# panel.net
KiCad netlist of a schematic drawn in EAGLE
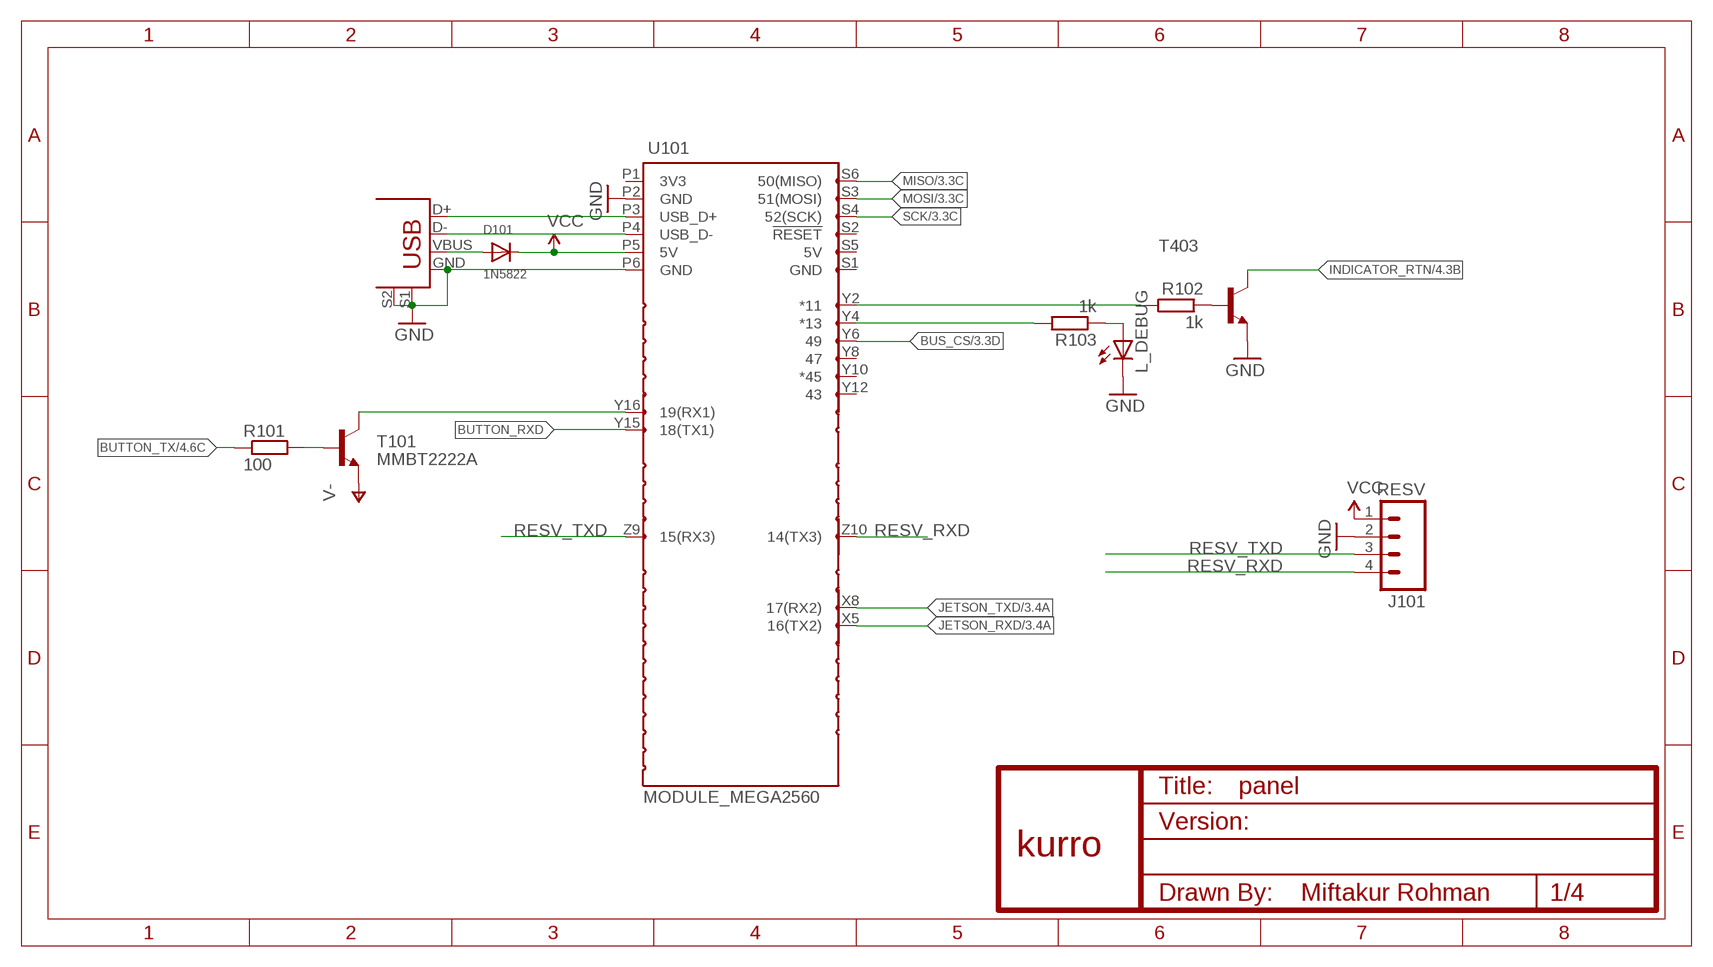
[diagram p0: schematic, sheet 1]
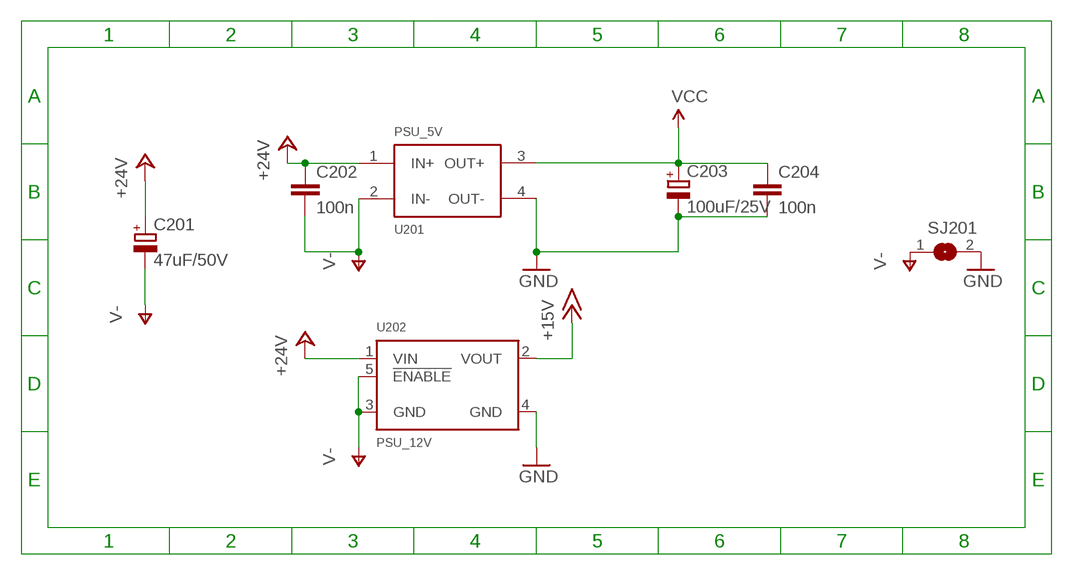
[diagram p1: schematic, sheet 2]
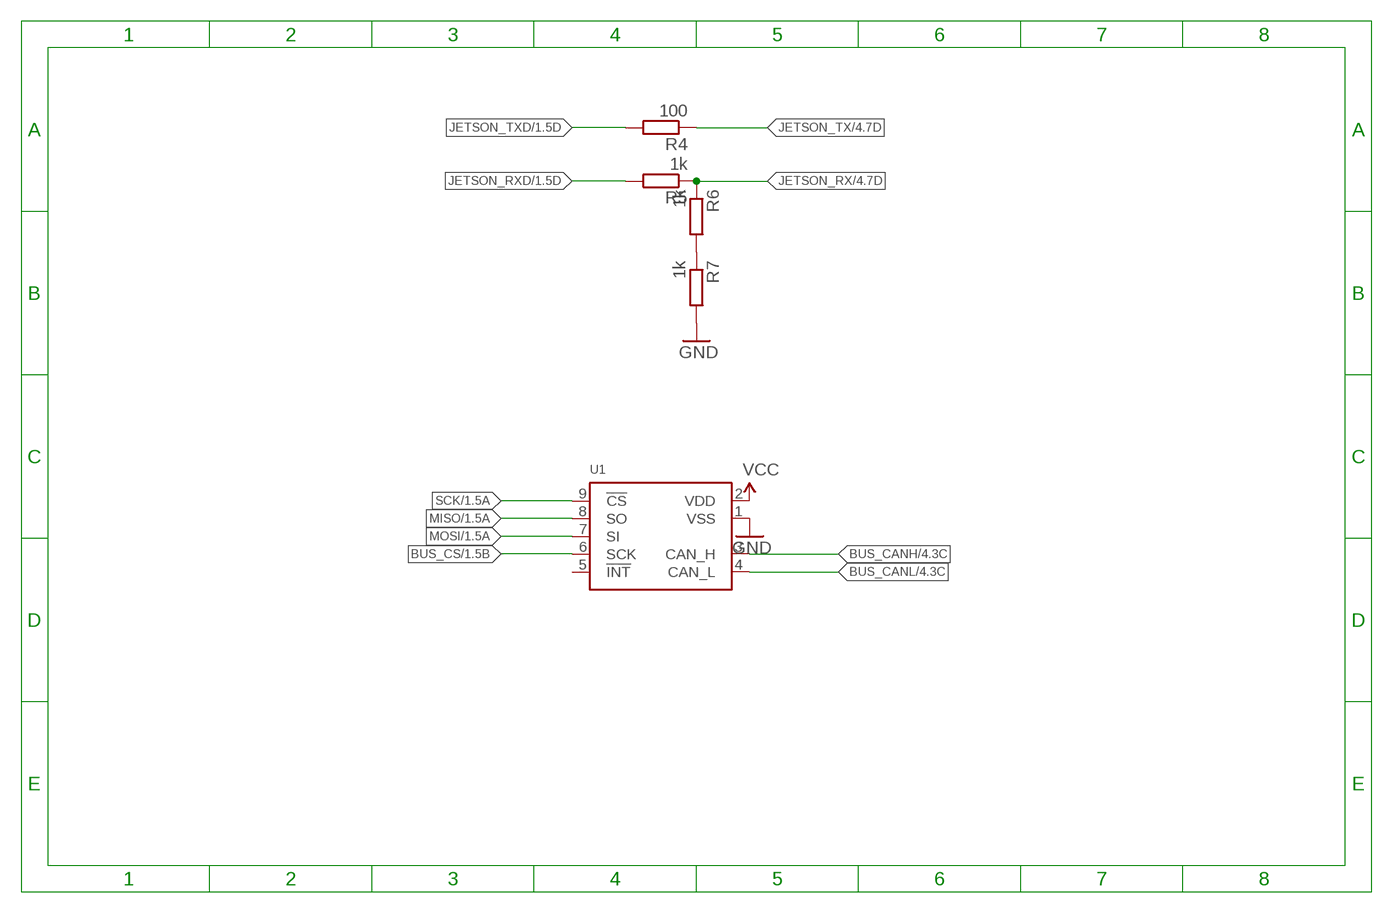
[diagram p2: schematic, sheet 3]
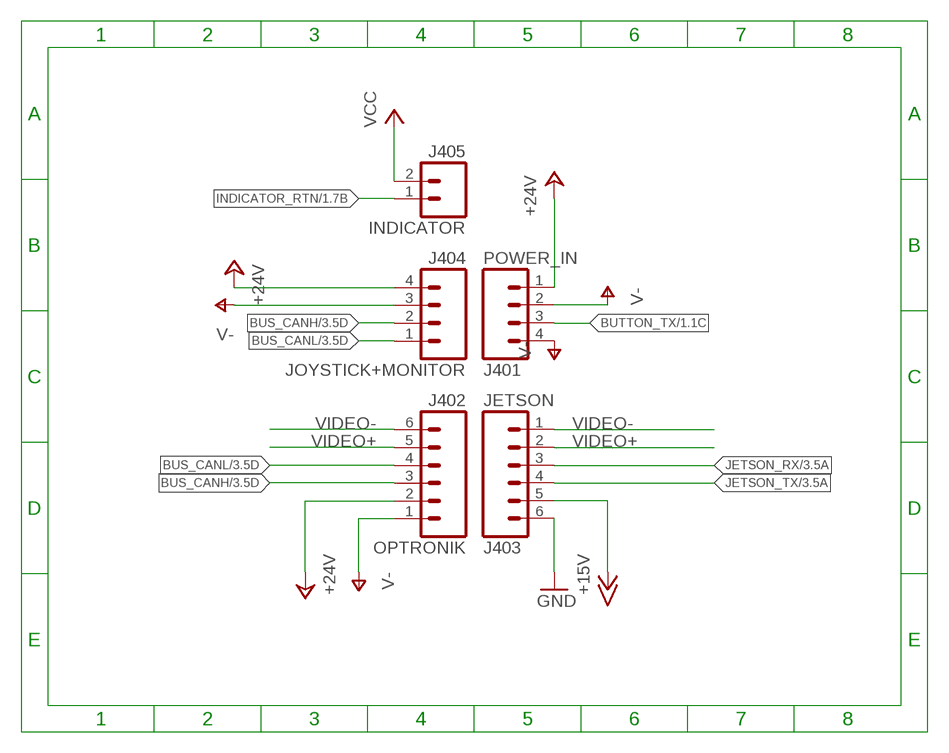
[diagram p3: schematic, sheet 4]

(export (version "E")
  (design (tool "Eeschema 10.0.6"))
  (components
    (comp (ref "D101")
      (value "1N5822")
      (footprint "eagle-import:SMADIODE")
      (libsource (lib "eagle-import") (part "DIODESMA"))
    )
    (comp (ref "J101")
      (value "RESV")
      (footprint "eagle-import:XH-4-RA")
      (libsource (lib "eagle-import") (part "M04-XH-RA"))
    )
    (comp (ref "L_DEBUG")
      (value "LED5MM")
      (footprint "eagle-import:LED5MM")
      (libsource (lib "eagle-import") (part "LED5MM"))
    )
    (comp (ref "R101")
      (value "100")
      (footprint "eagle-import:R0603")
      (libsource (lib "eagle-import") (part "R-EU_R0603"))
    )
    (comp (ref "R102")
      (value "1k")
      (footprint "eagle-import:R0603")
      (libsource (lib "eagle-import") (part "resistor_R-EU_R0603"))
    )
    (comp (ref "R103")
      (value "1k")
      (footprint "eagle-import:R0603")
      (libsource (lib "eagle-import") (part "resistor_R-EU_R0603"))
    )
    (comp (ref "T101")
      (value "MMBT2222A")
      (footprint "eagle-import:SOT23")
      (libsource (lib "eagle-import") (part "TRANSISTOR_NPNSOT23"))
    )
    (comp (ref "T403")
      (value "MMBT2222ALT1-NPN-SOT23-BEC")
      (footprint "eagle-import:SOT23-BEC")
      (libsource (lib "eagle-import") (part "-NPN-SOT23-BECMMBT2222ALT1"))
    )
    (comp (ref "U$1")
      (value "KURRO_FOOTPRINT")
      (footprint "eagle-import:KURRO-LOGO")
      (libsource (lib "eagle-import") (part "KURRO_FOOTPRINT"))
    )
    (comp (ref "U$2")
      (value "USB+SHIELD")
      (footprint "eagle-import:USB-B-PTH")
      (libsource (lib "eagle-import") (part "USB+SHIELD"))
    )
    (comp (ref "U$3")
      (value "MOD_MEGA_LAYOUT_SERIAL1")
      (footprint "eagle-import:MOD_MEGA_LAYOUT_SERIAL1")
      (libsource (lib "eagle-import") (part "MOD_MEGA_LAYOUT_SERIAL1"))
    )
    (comp (ref "U$4")
      (value "MOD_MEGA_LAYOUT_SERIAL2")
      (footprint "eagle-import:MOD_MEGA_LAYOUT_SERIAL2")
      (libsource (lib "eagle-import") (part "MOD_MEGA_LAYOUT_SERIAL2"))
    )
    (comp (ref "U$5")
      (value "MOD_MEGA_LAYOUT_SERIAL3")
      (footprint "eagle-import:MOD_MEGA_LAYOUT_SERIAL3")
      (libsource (lib "eagle-import") (part "MOD_MEGA_LAYOUT_SERIAL3"))
    )
    (comp (ref "U$6")
      (value "MOD_MEGA_LAYOUT_ICSP")
      (footprint "eagle-import:MOD_MEGA_LAYOUT_ICSP")
      (libsource (lib "eagle-import") (part "MOD_MEGA_LAYOUT_ICSP"))
    )
    (comp (ref "U$7")
      (value "MOD_MEGA_LAYOUT_Y_EVEN")
      (footprint "eagle-import:MOD_MEGA_LAYOUT_Y_EVEN")
      (libsource (lib "eagle-import") (part "MOD_MEGA_LAYOUT_Y_EVEN"))
    )
    (comp (ref "U101")
      (value "MODULE_MEGA2560")
      (footprint "eagle-import:MOD_MEGA_LAYOUT")
      (libsource (lib "eagle-import") (part "MOD_MEGA_LAYOUT"))
    )
    (comp (ref "C201")
      (value "47uF/50V")
      (footprint "eagle-import:E2,5-7")
      (libsource (lib "eagle-import") (part "CPOL-EUE2.5-7"))
    )
    (comp (ref "C202")
      (value "100n")
      (footprint "eagle-import:C0603")
      (libsource (lib "eagle-import") (part "C-EUC0603"))
    )
    (comp (ref "C203")
      (value "100uF/25V")
      (footprint "eagle-import:E2,5-7")
      (libsource (lib "eagle-import") (part "CPOL-EUE2.5-7"))
    )
    (comp (ref "C204")
      (value "100n")
      (footprint "eagle-import:C0603")
      (libsource (lib "eagle-import") (part "C-EUC0603"))
    )
    (comp (ref "SJ201")
      (value "SJS")
      (footprint "eagle-import:SJS")
      (libsource (lib "eagle-import") (part "SJS"))
    )
    (comp (ref "U201")
      (value "PSU_5V")
      (footprint "eagle-import:MP1584_MIN")
      (libsource (lib "eagle-import") (part "MP1584_MIN"))
    )
    (comp (ref "U202")
      (value "PSU_12V")
      (footprint "eagle-import:MOD_LM2596")
      (libsource (lib "eagle-import") (part "MOD_LM2596"))
    )
    (comp (ref "R4")
      (value "100")
      (footprint "eagle-import:R0603")
      (libsource (lib "eagle-import") (part "R-EU_R0603"))
    )
    (comp (ref "R5")
      (value "1k")
      (footprint "eagle-import:R0603")
      (libsource (lib "eagle-import") (part "R-EU_R0603"))
    )
    (comp (ref "R6")
      (value "1k")
      (footprint "eagle-import:R0603")
      (libsource (lib "eagle-import") (part "R-EU_R0603"))
    )
    (comp (ref "R7")
      (value "1k")
      (footprint "eagle-import:R0603")
      (libsource (lib "eagle-import") (part "R-EU_R0603"))
    )
    (comp (ref "U1")
      (value "MOD_MCP2515_NH")
      (footprint "eagle-import:MCP2515_CAN2")
      (libsource (lib "eagle-import") (part "MOD_MCP2515_NH"))
    )
    (comp (ref "J401")
      (value "POWER_IN")
      (footprint "eagle-import:XH-4-RA")
      (libsource (lib "eagle-import") (part "M04-XH-RA"))
    )
    (comp (ref "J402")
      (value "OPTRONIK")
      (footprint "eagle-import:XH-6-RA")
      (libsource (lib "eagle-import") (part "M06-XH-RA"))
    )
    (comp (ref "J403")
      (value "JETSON")
      (footprint "eagle-import:XH-6-RA")
      (libsource (lib "eagle-import") (part "M06-XH-RA"))
    )
    (comp (ref "J404")
      (value "JOYSTICK+MONITOR")
      (footprint "eagle-import:XH-4-RA")
      (libsource (lib "eagle-import") (part "M04-XH-RA"))
    )
    (comp (ref "J405")
      (value "INDICATOR")
      (footprint "eagle-import:XH-2-RA")
      (libsource (lib "eagle-import") (part "M02-XH-RA"))
    )
  )
  (nets
    (net (code "1") (name "+15V") (class "Default")
      (node (ref "J403") (pin "5") (pinfunction "5_5") (pintype "passive"))
      (node (ref "U202") (pin "2") (pinfunction "VOUT_2") (pintype "output"))
    )
    (net (code "2") (name "+24V") (class "Default")
      (node (ref "C201") (pin "+") (pinfunction "+_+") (pintype "passive"))
      (node (ref "C202") (pin "1") (pinfunction "1_1") (pintype "passive"))
      (node (ref "J401") (pin "1") (pinfunction "1_1") (pintype "passive"))
      (node (ref "J402") (pin "2") (pinfunction "2_2") (pintype "passive"))
      (node (ref "J404") (pin "4") (pinfunction "4_4") (pintype "passive"))
      (node (ref "U201") (pin "1") (pinfunction "IN+_1") (pintype "bidirectional"))
      (node (ref "U202") (pin "1") (pinfunction "VIN_1") (pintype "power_in"))
    )
    (net (code "3") (name "BUS_CANH") (class "Default")
      (node (ref "J402") (pin "3") (pinfunction "3_3") (pintype "passive"))
      (node (ref "J404") (pin "2") (pinfunction "2_2") (pintype "passive"))
      (node (ref "U1") (pin "3") (pinfunction "CAN_H_3") (pintype "bidirectional"))
    )
    (net (code "4") (name "BUS_CANL") (class "Default")
      (node (ref "J402") (pin "4") (pinfunction "4_4") (pintype "passive"))
      (node (ref "J404") (pin "1") (pinfunction "1_1") (pintype "passive"))
      (node (ref "U1") (pin "4") (pinfunction "CAN_L_4") (pintype "bidirectional"))
    )
    (net (code "5") (name "BUS_CS") (class "Default")
      (node (ref "U$7") (pin "Y6") (pinfunction "49_Y6") (pintype "bidirectional"))
      (node (ref "U1") (pin "6") (pinfunction "SCK_6") (pintype "bidirectional"))
    )
    (net (code "6") (name "BUTTON_RXD") (class "Default")
      (node (ref "U$3") (pin "Y15") (pinfunction "18(TX1)_Y15") (pintype "bidirectional"))
    )
    (net (code "7") (name "BUTTON_TX") (class "Default")
      (node (ref "J401") (pin "3") (pinfunction "3_3") (pintype "passive"))
      (node (ref "R101") (pin "1") (pinfunction "1_1") (pintype "passive"))
    )
    (net (code "8") (name "GND") (class "Default")
      (node (ref "C203") (pin "-") (pinfunction "-_-") (pintype "passive"))
      (node (ref "C204") (pin "2") (pinfunction "2_2") (pintype "passive"))
      (node (ref "J101") (pin "2") (pinfunction "2_2") (pintype "passive"))
      (node (ref "J403") (pin "6") (pinfunction "6_6") (pintype "passive"))
      (node (ref "L_DEBUG") (pin "K") (pinfunction "C_K") (pintype "passive"))
      (node (ref "R7") (pin "2") (pinfunction "2_2") (pintype "passive"))
      (node (ref "SJ201") (pin "2") (pinfunction "2_2") (pintype "passive"))
      (node (ref "T403") (pin "E") (pinfunction "E_E") (pintype "passive"))
      (node (ref "U$2") (pin "GND") (pinfunction "GND_GND") (pintype "bidirectional"))
      (node (ref "U$2") (pin "S1") (pinfunction "P$1_S1") (pintype "bidirectional"))
      (node (ref "U$2") (pin "S2") (pinfunction "P$2_S2") (pintype "bidirectional"))
      (node (ref "U1") (pin "1") (pinfunction "VSS_1") (pintype "bidirectional"))
      (node (ref "U101") (pin "P2") (pinfunction "GND_P2") (pintype "bidirectional"))
      (node (ref "U101") (pin "P6") (pinfunction "GND_P6") (pintype "bidirectional"))
      (node (ref "U201") (pin "4") (pinfunction "OUT-_4") (pintype "bidirectional"))
      (node (ref "U202") (pin "4") (pinfunction "GND_4") (pintype "passive"))
    )
    (net (code "9") (name "INDICATOR_RTN") (class "Default")
      (node (ref "J405") (pin "1") (pinfunction "1_1") (pintype "passive"))
      (node (ref "T403") (pin "C") (pinfunction "C_C") (pintype "passive"))
    )
    (net (code "10") (name "JETSON_RX") (class "Default")
      (node (ref "J403") (pin "3") (pinfunction "3_3") (pintype "passive"))
      (node (ref "R5") (pin "1") (pinfunction "1_1") (pintype "passive"))
      (node (ref "R6") (pin "1") (pinfunction "1_1") (pintype "passive"))
    )
    (net (code "11") (name "JETSON_RXD") (class "Default")
      (node (ref "R5") (pin "2") (pinfunction "2_2") (pintype "passive"))
      (node (ref "U$4") (pin "X5") (pinfunction "16(TX2)_X5") (pintype "bidirectional"))
    )
    (net (code "12") (name "JETSON_TX") (class "Default")
      (node (ref "J403") (pin "4") (pinfunction "4_4") (pintype "passive"))
      (node (ref "R4") (pin "1") (pinfunction "1_1") (pintype "passive"))
    )
    (net (code "13") (name "JETSON_TXD") (class "Default")
      (node (ref "R4") (pin "2") (pinfunction "2_2") (pintype "passive"))
      (node (ref "U$4") (pin "X8") (pinfunction "17(RX2)_X8") (pintype "bidirectional"))
    )
    (net (code "14") (name "MISO") (class "Default")
      (node (ref "U$6") (pin "S6") (pinfunction "50(MISO)_S6") (pintype "bidirectional"))
      (node (ref "U1") (pin "8") (pinfunction "SO_8") (pintype "bidirectional"))
    )
    (net (code "15") (name "MOSI") (class "Default")
      (node (ref "U$6") (pin "S3") (pinfunction "51(MOSI)_S3") (pintype "bidirectional"))
      (node (ref "U1") (pin "7") (pinfunction "SI_7") (pintype "bidirectional"))
    )
    (net (code "16") (name "Net-(D101-PadA)") (class "Default")
      (node (ref "D101") (pin "A") (pinfunction "A_A") (pintype "passive"))
      (node (ref "U$2") (pin "VBUS") (pinfunction "VBUS_VBUS") (pintype "bidirectional"))
    )
    (net (code "17") (name "Net-(L_DEBUG-PadA)") (class "Default")
      (node (ref "L_DEBUG") (pin "A") (pinfunction "A_A") (pintype "passive"))
      (node (ref "R103") (pin "1") (pinfunction "1_1") (pintype "passive"))
    )
    (net (code "18") (name "Net-(R6-Pad2)") (class "Default")
      (node (ref "R6") (pin "2") (pinfunction "2_2") (pintype "passive"))
      (node (ref "R7") (pin "1") (pinfunction "1_1") (pintype "passive"))
    )
    (net (code "19") (name "Net-(R102-Pad1)") (class "Default")
      (node (ref "R102") (pin "1") (pinfunction "1_1") (pintype "passive"))
      (node (ref "T403") (pin "B") (pinfunction "B_B") (pintype "passive"))
    )
    (net (code "20") (name "Net-(T101-B)") (class "Default")
      (node (ref "R101") (pin "2") (pinfunction "2_2") (pintype "passive"))
      (node (ref "T101") (pin "1") (pinfunction "B_1") (pintype "passive"))
    )
    (net (code "21") (name "Net-(T101-C)") (class "Default")
      (node (ref "T101") (pin "3") (pinfunction "C_3") (pintype "passive"))
      (node (ref "U$3") (pin "Y16") (pinfunction "19(RX1)_Y16") (pintype "bidirectional"))
    )
    (net (code "22") (name "Net-(U$7-*11)") (class "Default")
      (node (ref "R102") (pin "2") (pinfunction "2_2") (pintype "passive"))
      (node (ref "U$7") (pin "Y2") (pinfunction "*11_Y2") (pintype "bidirectional"))
    )
    (net (code "23") (name "Net-(U$7-*13)") (class "Default")
      (node (ref "R103") (pin "2") (pinfunction "2_2") (pintype "passive"))
      (node (ref "U$7") (pin "Y4") (pinfunction "*13_Y4") (pintype "bidirectional"))
    )
    (net (code "24") (name "Net-(U101-USB_D+)") (class "Default")
      (node (ref "U$2") (pin "D+") (pinfunction "D+_D+") (pintype "bidirectional"))
      (node (ref "U101") (pin "P3") (pinfunction "USB_D+_P3") (pintype "bidirectional"))
    )
    (net (code "25") (name "Net-(U101-USB_D-)") (class "Default")
      (node (ref "U$2") (pin "D-") (pinfunction "D-_D-") (pintype "bidirectional"))
      (node (ref "U101") (pin "P4") (pinfunction "USB_D-_P4") (pintype "bidirectional"))
    )
    (net (code "26") (name "RESV_RXD") (class "Default")
      (node (ref "J101") (pin "4") (pinfunction "4_4") (pintype "passive"))
      (node (ref "U$5") (pin "Z10") (pinfunction "14(TX3)_Z10") (pintype "bidirectional"))
    )
    (net (code "27") (name "RESV_TXD") (class "Default")
      (node (ref "J101") (pin "3") (pinfunction "3_3") (pintype "passive"))
      (node (ref "U$5") (pin "Z9") (pinfunction "15(RX3)_Z9") (pintype "bidirectional"))
    )
    (net (code "28") (name "SCK") (class "Default")
      (node (ref "U$6") (pin "S4") (pinfunction "52(SCK)_S4") (pintype "bidirectional"))
      (node (ref "U1") (pin "9") (pinfunction "~{CS}_9") (pintype "bidirectional"))
    )
    (net (code "29") (name "V-") (class "Default")
      (node (ref "C201") (pin "-") (pinfunction "-_-") (pintype "passive"))
      (node (ref "C202") (pin "2") (pinfunction "2_2") (pintype "passive"))
      (node (ref "J401") (pin "2") (pinfunction "2_2") (pintype "passive"))
      (node (ref "J401") (pin "4") (pinfunction "4_4") (pintype "passive"))
      (node (ref "J402") (pin "1") (pinfunction "1_1") (pintype "passive"))
      (node (ref "J404") (pin "3") (pinfunction "3_3") (pintype "passive"))
      (node (ref "SJ201") (pin "1") (pinfunction "1_1") (pintype "passive"))
      (node (ref "T101") (pin "2") (pinfunction "E_2") (pintype "passive"))
      (node (ref "U201") (pin "2") (pinfunction "IN-_2") (pintype "bidirectional"))
      (node (ref "U202") (pin "3") (pinfunction "GND_3") (pintype "passive"))
      (node (ref "U202") (pin "5") (pinfunction "~{ENABLE}_5") (pintype "input"))
    )
    (net (code "30") (name "VCC") (class "Default")
      (node (ref "C203") (pin "+") (pinfunction "+_+") (pintype "passive"))
      (node (ref "C204") (pin "1") (pinfunction "1_1") (pintype "passive"))
      (node (ref "D101") (pin "C") (pinfunction "C_C") (pintype "passive"))
      (node (ref "J101") (pin "1") (pinfunction "1_1") (pintype "passive"))
      (node (ref "J405") (pin "2") (pinfunction "2_2") (pintype "passive"))
      (node (ref "U1") (pin "2") (pinfunction "VDD_2") (pintype "bidirectional"))
      (node (ref "U101") (pin "P5") (pinfunction "5V_P5") (pintype "bidirectional"))
      (node (ref "U201") (pin "3") (pinfunction "OUT+_3") (pintype "bidirectional"))
    )
    (net (code "31") (name "VIDEO+") (class "Default")
      (node (ref "J402") (pin "5") (pinfunction "5_5") (pintype "passive"))
      (node (ref "J403") (pin "2") (pinfunction "2_2") (pintype "passive"))
    )
    (net (code "32") (name "VIDEO-") (class "Default")
      (node (ref "J402") (pin "6") (pinfunction "6_6") (pintype "passive"))
      (node (ref "J403") (pin "1") (pinfunction "1_1") (pintype "passive"))
    )
    (net (code "33") (name "unconnected-(U$6-5V-PadS5)") (class "Default")
      (node (ref "U$6") (pin "S5") (pinfunction "5V_S5") (pintype "bidirectional"))
    )
    (net (code "34") (name "unconnected-(U$6-GND-PadS1)") (class "Default")
      (node (ref "U$6") (pin "S1") (pinfunction "GND_S1") (pintype "bidirectional"))
    )
    (net (code "35") (name "unconnected-(U$6-~{RESET}-PadS2)") (class "Default")
      (node (ref "U$6") (pin "S2") (pinfunction "~{RESET}_S2") (pintype "bidirectional"))
    )
    (net (code "36") (name "unconnected-(U$7-*45-PadY10)") (class "Default")
      (node (ref "U$7") (pin "Y10") (pinfunction "*45_Y10") (pintype "bidirectional"))
    )
    (net (code "37") (name "unconnected-(U$7-43-PadY12)") (class "Default")
      (node (ref "U$7") (pin "Y12") (pinfunction "43_Y12") (pintype "bidirectional"))
    )
    (net (code "38") (name "unconnected-(U$7-47-PadY8)") (class "Default")
      (node (ref "U$7") (pin "Y8") (pinfunction "47_Y8") (pintype "bidirectional"))
    )
    (net (code "39") (name "unconnected-(U1-~{INT}-Pad5)") (class "Default")
      (node (ref "U1") (pin "5") (pinfunction "~{INT}_5") (pintype "bidirectional"))
    )
    (net (code "40") (name "unconnected-(U101-3V3-PadP1)") (class "Default")
      (node (ref "U101") (pin "P1") (pinfunction "3V3_P1") (pintype "bidirectional"))
    )
  )
)
